# Sheet0.net
KiCad netlist of a schematic drawn in Altium Designer
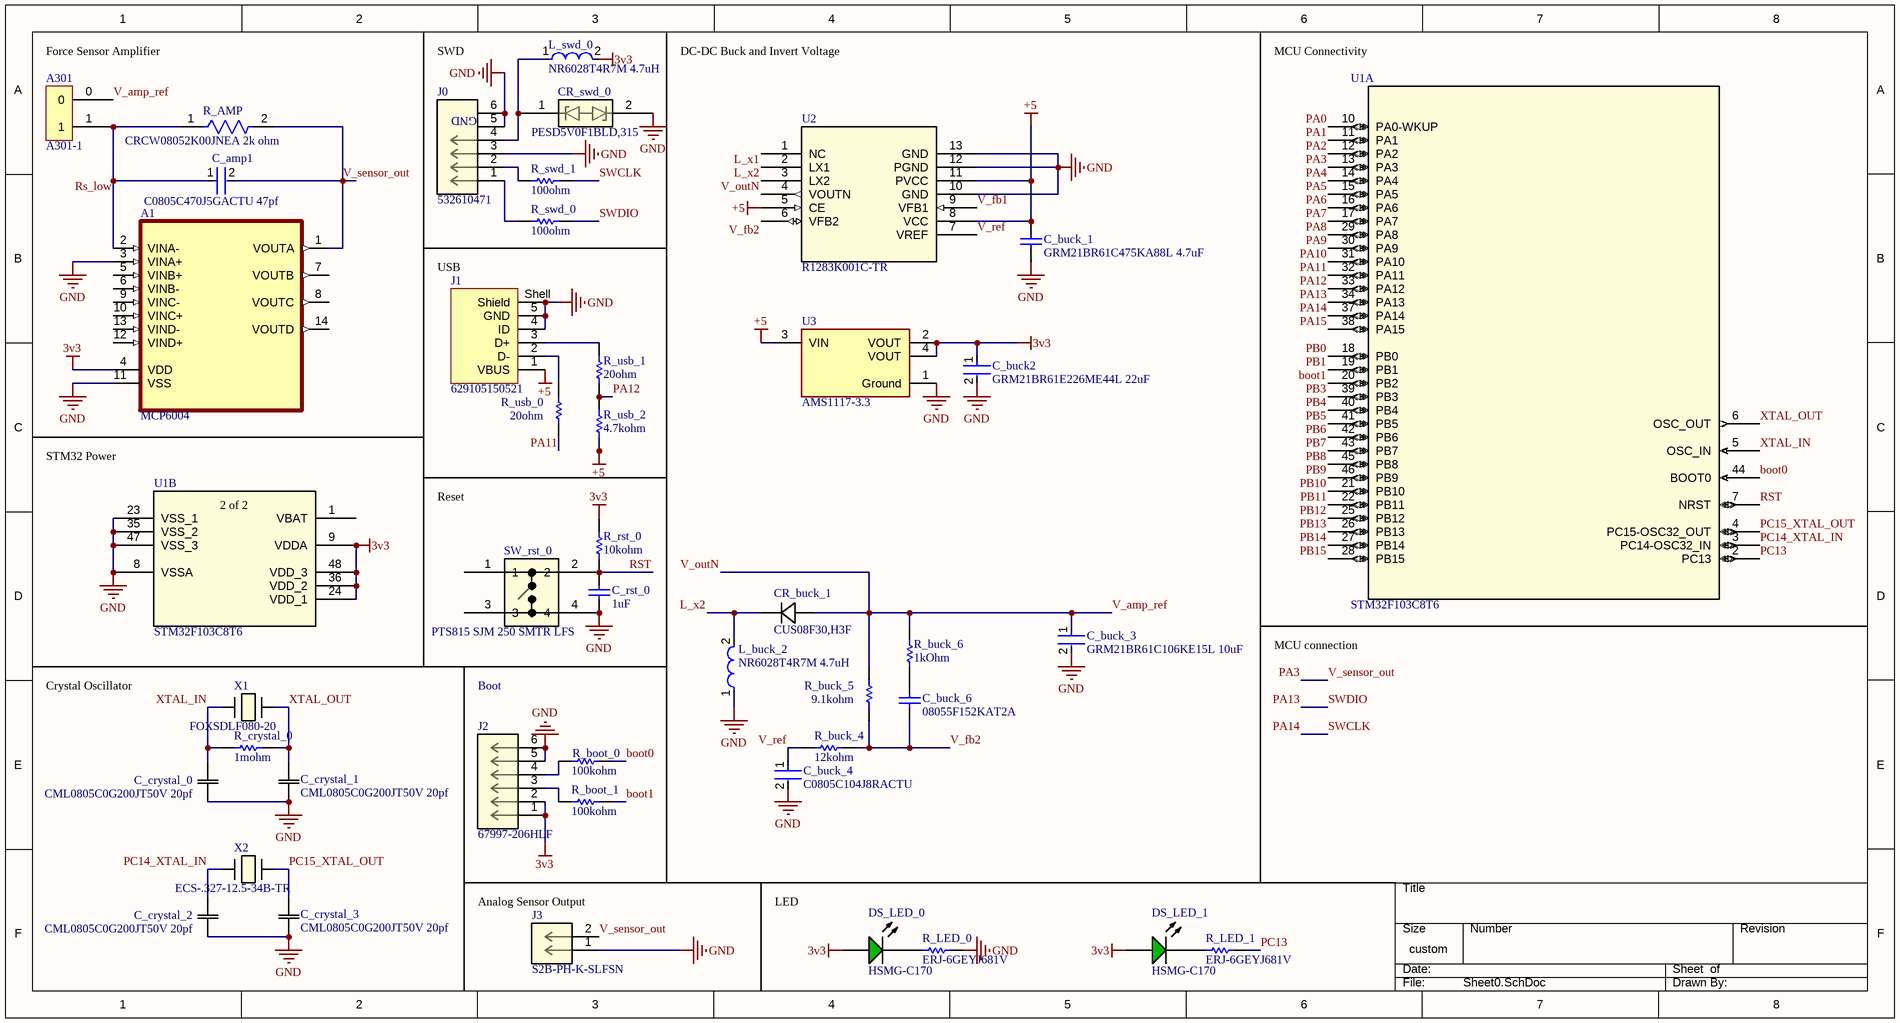
[diagram p0: Sheet0.SchDoc]

(export (version "E")
  (design (tool "Eeschema 10.0.6"))
  (components
    (comp (ref "A1")
      (value "MCP6004")
      (footprint "SOP65P640X120-14N")
      (libsource (lib "Schlib") (part "MCP6004"))
    )
    (comp (ref "A301") (value "A301-1") (footprint "A301-1") (libsource (lib "Schlib") (part "A301-1")))
    (comp (ref "CR_buck_1")
      (value "CUS08F30,H3F")
      (footprint "USC_TOS")
      (description "No Description Available")
      (libsource (lib "Schlib") (part "CUS08F30,H3F"))
    )
    (comp (ref "CR_swd_0")
      (value "PESD5V0F1BLD,315")
      (footprint "DFN1006D-2_SOD882D_NEX")
      (description "No Description Available")
      (libsource (lib "Schlib") (part "PESD5V0F1BLD,315"))
    )
    (comp (ref "C_amp1")
      (value "C0805C470J5GACTU 47pf")
      (footprint "FP-C0805C-DN-MFG")
      (description "CAP CER 47PF 50V C0G/NP0 0805")
      (fields
        (field (name "MANUFACTURER") "KEMET")
        (field (name "MANUFACTURER PART NUMBER") "C0805C470J5GACTU")
      )
      (libsource (lib "Altium Content Vault") (part "b4654b650e69147ec39a6b967a45e02"))
    )
    (comp (ref "C_buck2")
      (value "GRM21BR61E226ME44L 22uF")
      (footprint "FP-GRM21B-0_2-e0_2_0_7-IPC_B")
      (description "Chip Multilayer Ceramic Capacitors for General Purpose, 0805, 22uF, X5R, 15%, 20%, 25V")
      (fields (field (name "TOLERANCE") "20%") (field (name "VOLTAGE") "25V"))
      (libsource (lib "Altium Content Vault") (part "b4654b650e69147ec39a6b967a45e02"))
    )
    (comp (ref "C_buck_1")
      (value "GRM21BR61C475KA88L 4.7uF")
      (footprint "CAPC2013X135X45LL10T25")
      (description "Chip Capacitor, 4.7 uF, +/- 10%, 16 V, -55 to 85 degC, 0805 (2012 Metric), RoHS, Tape and Reel")
      (fields (field (name "TOLERANCE") "10%") (field (name "PARTNUMBER") "GRM21BR61C475KA88L"))
      (libsource (lib "Altium Content Vault") (part "CAP-NP-2"))
    )
    (comp (ref "C_buck_3")
      (value "GRM21BR61C106KE15L 10uF")
      (footprint "FP-GRM21B-0_1-IPC_C")
      (description "Chip Multilayer Ceramic Capacitors for General Purpose, 0805, 10uF, X5R, 15%, 10%, 16V")
      (fields (field (name "TOLERANCE") "10%") (field (name "VOLTAGE") "16V"))
      (libsource (lib "Altium Content Vault") (part "b4654b650e69147ec39a6b967a45e02"))
    )
    (comp (ref "C_buck_4")
      (value "C0805C104J8RACTU")
      (footprint "FP-C0805C-DN-MFG")
      (description "CAP CER 0.1UF 10V 5% X7R 0805")
      (fields (field (name "MANUFACTURER") "KEMET") (field (name "TOLERANCE") "0.05"))
      (libsource (lib "Altium Content Vault") (part "b4654b650e69147ec39a6b967a45e02"))
    )
    (comp (ref "C_buck_6")
      (value "08055F152KAT2A")
      (footprint "CAPC2013X140X50ML20T25")
      (fields (field (name "MANUFACTURER") "AVX Interconnect / Elco"))
      (libsource (lib "Altium Content Vault") (part "CAP"))
    )
    (comp (ref "C_crystal_0")
      (value "CML0805C0G200JT50V 20pf")
      (footprint "CAP_CML_0805_.3pF-1500pF,4700pF_STP")
      (description "No Description Available")
      (libsource (lib "Schlib") (part "CML0805C0G200JT50V"))
    )
    (comp (ref "C_crystal_1")
      (value "CML0805C0G200JT50V 20pf")
      (footprint "CAP_CML_0805_.3pF-1500pF,4700pF_STP")
      (description "No Description Available")
      (libsource (lib "Schlib") (part "CML0805C0G200JT50V"))
    )
    (comp (ref "C_crystal_2")
      (value "CML0805C0G200JT50V 20pf")
      (footprint "CAP_CML_0805_.3pF-1500pF,4700pF_STP")
      (description "No Description Available")
      (libsource (lib "Schlib") (part "CML0805C0G200JT50V"))
    )
    (comp (ref "C_crystal_3")
      (value "CML0805C0G200JT50V 20pf")
      (footprint "CAP_CML_0805_.3pF-1500pF,4700pF_STP")
      (description "No Description Available")
      (libsource (lib "Schlib") (part "CML0805C0G200JT50V"))
    )
    (comp (ref "C_rst_0")
      (value "1uF")
      (footprint "CAPC2013X140X50ML20T25")
      (fields (field (name "MANUFACTURER") "Kemet") (field (name "PART NUMBER") "C0805C105K5RACTU"))
      (libsource (lib "Altium Content Vault") (part "CAP"))
    )
    (comp (ref "DS_LED_0")
      (value "HSMG-C170")
      (footprint "AVAG-HSMX-C170_V")
      (description "Chip LED, Green, 2.2 V, -40 to 85 degC, 2-Pin SMD, Pb-Free, Tape and Reel")
      (fields (field (name "MANUFACTURER") "Avago"))
      (libsource (lib "Altium Content Vault") (part "LED_GREEN_A1K2-2"))
    )
    (comp (ref "DS_LED_1")
      (value "HSMG-C170")
      (footprint "AVAG-HSMX-C170_V")
      (description "Chip LED, Green, 2.2 V, -40 to 85 degC, 2-Pin SMD, Pb-Free, Tape and Reel")
      (fields (field (name "MANUFACTURER") "Avago"))
      (libsource (lib "Altium Content Vault") (part "LED_GREEN_A1K2-2"))
    )
    (comp (ref "J0")
      (value "532610471")
      (footprint "CONN_532610001-SD_04_MOL")
      (description "No Description Available")
      (libsource (lib "Schlib") (part "532610471"))
    )
    (comp (ref "J1")
      (value "629105150521")
      (footprint "629105150521")
      (libsource (lib "Altium Content Vault") (part "Micro USB 2.0_Type B_Receptacle_1 Port"))
    )
    (comp (ref "J2")
      (value "67997-206HLF")
      (footprint "6Pins_AMP")
      (description "No Description Available")
      (libsource (lib "Schlib") (part "67997-206HLF"))
    )
    (comp (ref "J3")
      (value "S2B-PH-K-SLFSN")
      (footprint "CONN_S2B-PH-K-S_JST")
      (description "No Description Available")
      (libsource (lib "Schlib") (part "S2B-PH-K-SLFSN"))
    )
    (comp (ref "L_buck_2")
      (value "NR6028T4R7M 4.7uH")
      (footprint "FP-NR6028-MFG")
      (description "SMD Power Inductors 4.7uH ±20% 2.7A 40.3mΩ")
      (fields (field (name "TOLERANCE") "20%"))
      (libsource (lib "Altium Content Vault") (part "725321dda6339637d4d059423bc1c3c"))
    )
    (comp (ref "L_swd_0")
      (value "NR6028T4R7M 4.7uH")
      (footprint "FP-NR6028-MFG")
      (description "SMD Power Inductors 4.7uH ±20% 2.7A 40.3mΩ")
      (fields (field (name "TOLERANCE") "20%"))
      (libsource (lib "Altium Content Vault") (part "725321dda6339637d4d059423bc1c3c"))
    )
    (comp (ref "R_AMP")
      (value "CRCW08052K00JNEA 2k ohm")
      (footprint "FP-CRCW0805-e3-MFG")
      (description "RES Thick Film, 2kΩ, 5%, 0.125W, 200ppm/°C, 0805")
      (fields (field (name "TOLERANCE") "5%"))
      (libsource (lib "Altium Content Vault") (part "1029c3af85768c4190bb7ad29bc67b5"))
    )
    (comp (ref "R_boot_0")
      (value "100kohm")
      (footprint "RESC2013X70X40ML20T20")
      (fields (field (name "PART NUMBER") "ERJ-6ENF1003V") (field (name "MANUFACTURER") "Panasonic"))
      (libsource (lib "Altium Content Vault") (part "RES"))
    )
    (comp (ref "R_boot_1")
      (value "100kohm")
      (footprint "RESC2013X70X40ML20T20")
      (fields (field (name "PART NUMBER") "ERJ-6ENF1003V") (field (name "MANUFACTURER") "Panasonic"))
      (libsource (lib "Altium Content Vault") (part "RES"))
    )
    (comp (ref "R_buck_4")
      (value "12kohm")
      (footprint "RESC2013X60X40ML20T25")
      (fields (field (name "PART NUMBER") "ERA6AEB123V") (field (name "MANUFACTURER") "Panasonic"))
      (libsource (lib "Altium Content Vault") (part "RES"))
    )
    (comp (ref "R_buck_5")
      (value "9.1kohm")
      (footprint "RESC2013X70X40NL20T20")
      (fields (field (name "PART NUMBER") "ERJ6ENF9101V") (field (name "MANUFACTURER") "Panasonic"))
      (libsource (lib "Altium Content Vault") (part "RES"))
    )
    (comp (ref "R_buck_6")
      (value "1kOhm")
      (footprint "RESC2013X60X35ML10T20")
      (description "Chip Resistor, 1 KOhm, +/- 1%, 125 mW, -55 to 155 degC, 0805 (2012 Metric), RoHS, Tape and Reel")
      (fields (field (name "TOLERANCE") "1%") (field (name "MANUFACTURER") "Yageo"))
      (libsource (lib "Altium Content Vault") (part "RES-2"))
    )
    (comp (ref "R_crystal_0")
      (value "1mohm")
      (footprint "RESC2013X50X30LL20T20")
      (fields (field (name "MANUFACTURER") "Vishay Dale") (field (name "PART NUMBER") "CRCW08051M00JNEA"))
      (libsource (lib "Altium Content Vault") (part "RES"))
    )
    (comp (ref "R_LED_0")
      (value "ERJ-6GEYJ681V")
      (footprint "RESC2013X70X40LL20T20")
      (fields (field (name "MANUFACTURER") "Panasonic"))
      (libsource (lib "Altium Content Vault") (part "RES"))
    )
    (comp (ref "R_LED_1")
      (value "ERJ-6GEYJ681V")
      (footprint "RESC2013X70X40LL20T20")
      (fields (field (name "MANUFACTURER") "Panasonic"))
      (libsource (lib "Altium Content Vault") (part "RES"))
    )
    (comp (ref "R_rst_0")
      (value "10kohm")
      (footprint "RESC2013X60X40LL20T25_A")
      (fields (field (name "TOLERANCE") "0.1%") (field (name "MANUFACTURER") "Panasonic"))
      (libsource (lib "Altium Content Vault") (part "RES-2"))
    )
    (comp (ref "R_swd_0")
      (value "100ohm")
      (footprint "RESC2013X60X40ML20T25")
      (fields (field (name "MANUFACTURER") "Panasonic") (field (name "PART NUMBER") "ERA6AEB101V"))
      (libsource (lib "Altium Content Vault") (part "RES"))
    )
    (comp (ref "R_swd_1")
      (value "100ohm")
      (footprint "RESC2013X60X40ML20T25")
      (fields (field (name "MANUFACTURER") "Panasonic") (field (name "PART NUMBER") "ERA6AEB101V"))
      (libsource (lib "Altium Content Vault") (part "RES"))
    )
    (comp (ref "R_usb_0")
      (value "20ohm")
      (footprint "RESC2013X70X40ML20T20")
      (fields (field (name "MANUFACTURER") "Panasonic") (field (name "PART NUMBER") "ERJ-6ENF20R0V"))
      (libsource (lib "Altium Content Vault") (part "RES"))
    )
    (comp (ref "R_usb_1")
      (value "20ohm")
      (footprint "RESC2013X70X40ML20T20")
      (fields (field (name "MANUFACTURER") "Panasonic") (field (name "PART NUMBER") "ERJ-6ENF20R0V"))
      (libsource (lib "Altium Content Vault") (part "RES"))
    )
    (comp (ref "R_usb_2")
      (value "4.7kohm")
      (footprint "RESC2013X60X40ML20T25")
      (fields (field (name "PART NUMBER") "ERA6AEB472V") (field (name "MANUFACTURER") "Panasonic"))
      (libsource (lib "Altium Content Vault") (part "RES"))
    )
    (comp (ref "SW_rst_0")
      (value "PTS815 SJM 250 SMTR LFS")
      (footprint "SW4_PTS815 SJM 250 SMTR LFS_CNK")
      (description "No Description Available")
      (libsource (lib "Schlib") (part "PTS815 SJM 250 SMTR LFS"))
    )
    (comp (ref "U1")
      (value "STM32F103C8T6")
      (footprint "LQFP48_STM")
      (description "No Description Available")
      (libsource (lib "Schlib") (part "STM32F103C8T6"))
    )
    (comp (ref "U2")
      (value "R1283K001C-TR")
      (footprint "PE-DFNPL2730-12-180404_NMD")
      (description "No Description Available")
      (libsource (lib "Schlib") (part "R1283K001C-TR"))
    )
    (comp (ref "U3")
      (value "AMS1117-3.3")
      (footprint "FP-AMS1117-IPC_C")
      (description "LDO Voltage Regulators 1A, 3.3V")
      (fields
        (field (name "OCTOPART") "https://octopart.com/ams1117-3.3-advanced+monolithic+systems-25899300")
        (field (name "MANUFACTURER") "Advanced Monolithic Systems")
      )
      (libsource (lib "Altium Content Vault") (part "8bdbb5f8e77002000e30dd2845d0354"))
    )
    (comp (ref "X1")
      (value "FOXSDLF080-20")
      (footprint "CRYSTAL_HC49SDLF_FXT")
      (description "No Description Available")
      (libsource (lib "Schlib") (part "FOXSDLF080-20"))
    )
    (comp (ref "X2")
      (value "ECS-.327-12.5-34B-TR")
      (footprint "XTAL_ECS-31B_ECS")
      (description "No Description Available")
      (libsource (lib "Schlib") (part "ECS-.327-12.5-34B-TR"))
    )
  )
  (nets
    (net (code "1") (name "+5") (class "Default")
      (node (ref "C_buck_1") (pin "2") (pinfunction "2_2") (pintype "passive"))
      (node (ref "J1") (pin "1") (pinfunction "VBUS_1") (pintype "passive"))
      (node (ref "R_usb_2") (pin "1") (pinfunction "1_1") (pintype "passive"))
      (node (ref "U2") (pin "11") (pinfunction "PVCC_11") (pintype "power_in"))
      (node (ref "U2") (pin "5") (pinfunction "CE_5") (pintype "input"))
      (node (ref "U2") (pin "8") (pinfunction "VCC_8") (pintype "power_in"))
      (node (ref "U3") (pin "3") (pinfunction "VIN_3") (pintype "power_in"))
    )
    (net (code "2") (name "/L_x1") (class "Default")
      (node (ref "U2") (pin "2") (pinfunction "LX1_2") (pintype "power_in"))
    )
    (net (code "3") (name "/L_x2") (class "Default")
      (node (ref "CR_buck_1") (pin "1") (pinfunction "cathode_1") (pintype "passive"))
      (node (ref "L_buck_2") (pin "2") (pinfunction "2_2") (pintype "passive"))
      (node (ref "U2") (pin "3") (pinfunction "LX2_3") (pintype "power_in"))
    )
    (net (code "4") (name "/PA0") (class "Default")
      (node (ref "U1") (pin "10") (pinfunction "PA0-WKUP_10") (pintype "bidirectional"))
    )
    (net (code "5") (name "/PA1") (class "Default")
      (node (ref "U1") (pin "11") (pinfunction "PA1_11") (pintype "bidirectional"))
    )
    (net (code "6") (name "/PA2") (class "Default")
      (node (ref "U1") (pin "12") (pinfunction "PA2_12") (pintype "bidirectional"))
    )
    (net (code "7") (name "/PA3") (class "Default")
      (node (ref "A1") (pin "1") (pinfunction "VOUTA_1") (pintype "output"))
      (node (ref "C_amp1") (pin "2") (pinfunction "2_2") (pintype "passive"))
      (node (ref "J3") (pin "2") (pinfunction "2_2") (pintype "passive"))
      (node (ref "R_AMP") (pin "2") (pinfunction "2_2") (pintype "passive"))
      (node (ref "U1") (pin "13") (pinfunction "PA3_13") (pintype "bidirectional"))
    )
    (net (code "8") (name "/PA4") (class "Default")
      (node (ref "U1") (pin "14") (pinfunction "PA4_14") (pintype "bidirectional"))
    )
    (net (code "9") (name "/PA5") (class "Default")
      (node (ref "U1") (pin "15") (pinfunction "PA5_15") (pintype "bidirectional"))
    )
    (net (code "10") (name "/PA6") (class "Default")
      (node (ref "U1") (pin "16") (pinfunction "PA6_16") (pintype "bidirectional"))
    )
    (net (code "11") (name "/PA7") (class "Default")
      (node (ref "U1") (pin "17") (pinfunction "PA7_17") (pintype "bidirectional"))
    )
    (net (code "12") (name "/PA8") (class "Default")
      (node (ref "U1") (pin "29") (pinfunction "PA8_29") (pintype "bidirectional"))
    )
    (net (code "13") (name "/PA9") (class "Default")
      (node (ref "U1") (pin "30") (pinfunction "PA9_30") (pintype "bidirectional"))
    )
    (net (code "14") (name "/PA10") (class "Default")
      (node (ref "U1") (pin "31") (pinfunction "PA10_31") (pintype "bidirectional"))
    )
    (net (code "15") (name "/PA11") (class "Default")
      (node (ref "R_usb_0") (pin "1") (pinfunction "1_1") (pintype "passive"))
      (node (ref "U1") (pin "32") (pinfunction "PA11_32") (pintype "bidirectional"))
    )
    (net (code "16") (name "/PA12") (class "Default")
      (node (ref "R_usb_1") (pin "1") (pinfunction "1_1") (pintype "passive"))
      (node (ref "R_usb_2") (pin "2") (pinfunction "2_2") (pintype "passive"))
      (node (ref "U1") (pin "33") (pinfunction "PA12_33") (pintype "bidirectional"))
    )
    (net (code "17") (name "/PA13") (class "Default")
      (node (ref "R_swd_0") (pin "2") (pinfunction "2_2") (pintype "passive"))
      (node (ref "U1") (pin "34") (pinfunction "PA13_34") (pintype "bidirectional"))
    )
    (net (code "18") (name "/PA14") (class "Default")
      (node (ref "R_swd_1") (pin "2") (pinfunction "2_2") (pintype "passive"))
      (node (ref "U1") (pin "37") (pinfunction "PA14_37") (pintype "bidirectional"))
    )
    (net (code "19") (name "/PA15") (class "Default")
      (node (ref "U1") (pin "38") (pinfunction "PA15_38") (pintype "bidirectional"))
    )
    (net (code "20") (name "/PB0") (class "Default")
      (node (ref "U1") (pin "18") (pinfunction "PB0_18") (pintype "bidirectional"))
    )
    (net (code "21") (name "/PB1") (class "Default")
      (node (ref "U1") (pin "19") (pinfunction "PB1_19") (pintype "bidirectional"))
    )
    (net (code "22") (name "/PB3") (class "Default")
      (node (ref "U1") (pin "39") (pinfunction "PB3_39") (pintype "bidirectional"))
    )
    (net (code "23") (name "/PB4") (class "Default")
      (node (ref "U1") (pin "40") (pinfunction "PB4_40") (pintype "bidirectional"))
    )
    (net (code "24") (name "/PB5") (class "Default")
      (node (ref "U1") (pin "41") (pinfunction "PB5_41") (pintype "bidirectional"))
    )
    (net (code "25") (name "/PB6") (class "Default")
      (node (ref "U1") (pin "42") (pinfunction "PB6_42") (pintype "bidirectional"))
    )
    (net (code "26") (name "/PB7") (class "Default")
      (node (ref "U1") (pin "43") (pinfunction "PB7_43") (pintype "bidirectional"))
    )
    (net (code "27") (name "/PB8") (class "Default")
      (node (ref "U1") (pin "45") (pinfunction "PB8_45") (pintype "bidirectional"))
    )
    (net (code "28") (name "/PB9") (class "Default")
      (node (ref "U1") (pin "46") (pinfunction "PB9_46") (pintype "bidirectional"))
    )
    (net (code "29") (name "/PB10") (class "Default")
      (node (ref "U1") (pin "21") (pinfunction "PB10_21") (pintype "bidirectional"))
    )
    (net (code "30") (name "/PB11") (class "Default")
      (node (ref "U1") (pin "22") (pinfunction "PB11_22") (pintype "bidirectional"))
    )
    (net (code "31") (name "/PB12") (class "Default")
      (node (ref "U1") (pin "25") (pinfunction "PB12_25") (pintype "bidirectional"))
    )
    (net (code "32") (name "/PB13") (class "Default")
      (node (ref "U1") (pin "26") (pinfunction "PB13_26") (pintype "bidirectional"))
    )
    (net (code "33") (name "/PB14") (class "Default")
      (node (ref "U1") (pin "27") (pinfunction "PB14_27") (pintype "bidirectional"))
    )
    (net (code "34") (name "/PB15") (class "Default")
      (node (ref "U1") (pin "28") (pinfunction "PB15_28") (pintype "bidirectional"))
    )
    (net (code "35") (name "/PC13") (class "Default")
      (node (ref "R_LED_1") (pin "2") (pinfunction "2_2") (pintype "passive"))
      (node (ref "U1") (pin "2") (pinfunction "PC13_2") (pintype "bidirectional"))
    )
    (net (code "36") (name "/PC14_XTAL_IN") (class "Default")
      (node (ref "C_crystal_2") (pin "2") (pinfunction "2_2") (pintype "passive"))
      (node (ref "U1") (pin "3") (pinfunction "PC14-OSC32_IN_3") (pintype "bidirectional"))
      (node (ref "X2") (pin "1") (pinfunction "1_1") (pintype "passive"))
    )
    (net (code "37") (name "/PC15_XTAL_OUT") (class "Default")
      (node (ref "C_crystal_3") (pin "2") (pinfunction "2_2") (pintype "passive"))
      (node (ref "U1") (pin "4") (pinfunction "PC15-OSC32_OUT_4") (pintype "bidirectional"))
      (node (ref "X2") (pin "2") (pinfunction "2_2") (pintype "passive"))
    )
    (net (code "38") (name "/RST") (class "Default")
      (node (ref "C_rst_0") (pin "2") (pinfunction "2_2") (pintype "passive"))
      (node (ref "R_rst_0") (pin "1") (pinfunction "1_1") (pintype "passive"))
      (node (ref "SW_rst_0") (pin "2") (pinfunction "2_2") (pintype "passive"))
      (node (ref "U1") (pin "7") (pinfunction "NRST_7") (pintype "bidirectional"))
    )
    (net (code "39") (name "/Rs_low") (class "Default")
      (node (ref "A1") (pin "2") (pinfunction "VINA-_2") (pintype "input"))
      (node (ref "A301") (pin "1") (pinfunction "1_1") (pintype "passive"))
      (node (ref "C_amp1") (pin "1") (pinfunction "1_1") (pintype "passive"))
      (node (ref "R_AMP") (pin "1") (pinfunction "1_1") (pintype "passive"))
    )
    (net (code "40") (name "/V_amp_ref") (class "Default")
      (node (ref "A301") (pin "0") (pinfunction "0_0") (pintype "passive"))
      (node (ref "CR_buck_1") (pin "2") (pinfunction "anode_2") (pintype "passive"))
      (node (ref "C_buck_3") (pin "1") (pinfunction "1_1") (pintype "passive"))
      (node (ref "R_buck_5") (pin "2") (pinfunction "2_2") (pintype "passive"))
      (node (ref "R_buck_6") (pin "2") (pinfunction "2_2") (pintype "passive"))
      (node (ref "U2") (pin "4") (pinfunction "VOUTN_4") (pintype "output"))
    )
    (net (code "41") (name "/V_fb1") (class "Default")
      (node (ref "U2") (pin "9") (pinfunction "VFB1_9") (pintype "input"))
    )
    (net (code "42") (name "/V_fb2") (class "Default")
      (node (ref "C_buck_6") (pin "1") (pinfunction "1_1") (pintype "passive"))
      (node (ref "R_buck_4") (pin "2") (pinfunction "2_2") (pintype "passive"))
      (node (ref "R_buck_5") (pin "1") (pinfunction "1_1") (pintype "passive"))
      (node (ref "U2") (pin "6") (pinfunction "VFB2_6") (pintype "bidirectional"))
    )
    (net (code "43") (name "/V_ref") (class "Default")
      (node (ref "C_buck_4") (pin "1") (pinfunction "1_1") (pintype "passive"))
      (node (ref "R_buck_4") (pin "1") (pinfunction "1_1") (pintype "passive"))
      (node (ref "U2") (pin "7") (pinfunction "VREF_7") (pintype "power_in"))
    )
    (net (code "44") (name "/XTAL_IN") (class "Default")
      (node (ref "C_crystal_0") (pin "2") (pinfunction "2_2") (pintype "passive"))
      (node (ref "R_crystal_0") (pin "1") (pinfunction "1_1") (pintype "passive"))
      (node (ref "U1") (pin "5") (pinfunction "OSC_IN_5") (pintype "input"))
      (node (ref "X1") (pin "1") (pinfunction "1_1") (pintype "passive"))
    )
    (net (code "45") (name "/XTAL_OUT") (class "Default")
      (node (ref "C_crystal_1") (pin "2") (pinfunction "2_2") (pintype "passive"))
      (node (ref "R_crystal_0") (pin "2") (pinfunction "2_2") (pintype "passive"))
      (node (ref "U1") (pin "6") (pinfunction "OSC_OUT_6") (pintype "output"))
      (node (ref "X1") (pin "2") (pinfunction "2_2") (pintype "passive"))
    )
    (net (code "46") (name "/boot0") (class "Default")
      (node (ref "R_boot_0") (pin "2") (pinfunction "2_2") (pintype "passive"))
      (node (ref "U1") (pin "44") (pinfunction "BOOT0_44") (pintype "input"))
    )
    (net (code "47") (name "/boot1") (class "Default")
      (node (ref "R_boot_1") (pin "2") (pinfunction "2_2") (pintype "passive"))
      (node (ref "U1") (pin "20") (pinfunction "PB2_20") (pintype "bidirectional"))
    )
    (net (code "48") (name "3v3") (class "Default")
      (node (ref "A1") (pin "4") (pinfunction "VDD_4") (pintype "power_in"))
      (node (ref "C_buck2") (pin "1") (pinfunction "1_1") (pintype "passive"))
      (node (ref "DS_LED_0") (pin "1") (pinfunction "A_1") (pintype "passive"))
      (node (ref "DS_LED_1") (pin "1") (pinfunction "A_1") (pintype "passive"))
      (node (ref "J2") (pin "1") (pinfunction "1_1") (pintype "passive"))
      (node (ref "J2") (pin "2") (pinfunction "2_2") (pintype "passive"))
      (node (ref "L_swd_0") (pin "2") (pinfunction "2_2") (pintype "passive"))
      (node (ref "R_rst_0") (pin "2") (pinfunction "2_2") (pintype "passive"))
      (node (ref "U1") (pin "24") (pinfunction "VDD_1_24") (pintype "power_in"))
      (node (ref "U1") (pin "36") (pinfunction "VDD_2_36") (pintype "power_in"))
      (node (ref "U1") (pin "48") (pinfunction "VDD_3_48") (pintype "power_in"))
      (node (ref "U1") (pin "9") (pinfunction "VDDA_9") (pintype "power_in"))
      (node (ref "U3") (pin "2") (pinfunction "VOUT_2") (pintype "passive"))
      (node (ref "U3") (pin "4") (pinfunction "VOUT_4") (pintype "passive"))
    )
    (net (code "49") (name "GND") (class "Default")
      (node (ref "A1") (pin "11") (pinfunction "VSS_11") (pintype "passive"))
      (node (ref "A1") (pin "3") (pinfunction "VINA+_3") (pintype "input"))
      (node (ref "CR_swd_0") (pin "2") (pinfunction "2_2") (pintype "passive"))
      (node (ref "C_buck2") (pin "2") (pinfunction "2_2") (pintype "passive"))
      (node (ref "C_buck_1") (pin "1") (pinfunction "1_1") (pintype "passive"))
      (node (ref "C_buck_3") (pin "2") (pinfunction "2_2") (pintype "passive"))
      (node (ref "C_buck_4") (pin "2") (pinfunction "2_2") (pintype "passive"))
      (node (ref "C_crystal_0") (pin "1") (pinfunction "1_1") (pintype "passive"))
      (node (ref "C_crystal_1") (pin "1") (pinfunction "1_1") (pintype "passive"))
      (node (ref "C_crystal_2") (pin "1") (pinfunction "1_1") (pintype "passive"))
      (node (ref "C_crystal_3") (pin "1") (pinfunction "1_1") (pintype "passive"))
      (node (ref "C_rst_0") (pin "1") (pinfunction "1_1") (pintype "passive"))
      (node (ref "J0") (pin "3") (pinfunction "3_3") (pintype "passive"))
      (node (ref "J0") (pin "5") (pinfunction "5_5") (pintype "passive"))
      (node (ref "J0") (pin "6") (pinfunction "6_6") (pintype "passive"))
      (node (ref "J1") (pin "4") (pinfunction "ID_4") (pintype "passive"))
      (node (ref "J1") (pin "5") (pinfunction "GND_5") (pintype "passive"))
      (node (ref "J1") (pin "Shell") (pinfunction "Shield_Shell") (pintype "passive"))
      (node (ref "J2") (pin "5") (pinfunction "5_5") (pintype "passive"))
      (node (ref "J2") (pin "6") (pinfunction "6_6") (pintype "passive"))
      (node (ref "J3") (pin "1") (pinfunction "1_1") (pintype "passive"))
      (node (ref "L_buck_2") (pin "1") (pinfunction "1_1") (pintype "passive"))
      (node (ref "R_LED_0") (pin "2") (pinfunction "2_2") (pintype "passive"))
      (node (ref "SW_rst_0") (pin "4") (pinfunction "4_4") (pintype "passive"))
      (node (ref "U1") (pin "23") (pinfunction "VSS_1_23") (pintype "power_in"))
      (node (ref "U1") (pin "35") (pinfunction "VSS_2_35") (pintype "power_in"))
      (node (ref "U1") (pin "47") (pinfunction "VSS_3_47") (pintype "power_in"))
      (node (ref "U1") (pin "8") (pinfunction "VSSA_8") (pintype "power_in"))
      (node (ref "U2") (pin "10") (pinfunction "GND_10") (pintype "power_in"))
      (node (ref "U2") (pin "12") (pinfunction "PGND_12") (pintype "power_in"))
      (node (ref "U2") (pin "13") (pinfunction "GND_13") (pintype "power_in"))
      (node (ref "U3") (pin "1") (pinfunction "Ground_1") (pintype "power_in"))
    )
    (net (code "50") (name "Net-(CR_swd_0-Pad1)") (class "Default")
      (node (ref "CR_swd_0") (pin "1") (pinfunction "1_1") (pintype "passive"))
      (node (ref "J0") (pin "4") (pinfunction "4_4") (pintype "passive"))
      (node (ref "L_swd_0") (pin "1") (pinfunction "1_1") (pintype "passive"))
    )
    (net (code "51") (name "Net-(C_buck_6-Pad2)") (class "Default")
      (node (ref "C_buck_6") (pin "2") (pinfunction "2_2") (pintype "passive"))
      (node (ref "R_buck_6") (pin "1") (pinfunction "1_1") (pintype "passive"))
    )
    (net (code "52") (name "Net-(DS_LED_0-K)") (class "Default")
      (node (ref "DS_LED_0") (pin "2") (pinfunction "K_2") (pintype "passive"))
      (node (ref "R_LED_0") (pin "1") (pinfunction "1_1") (pintype "passive"))
    )
    (net (code "53") (name "Net-(DS_LED_1-K)") (class "Default")
      (node (ref "DS_LED_1") (pin "2") (pinfunction "K_2") (pintype "passive"))
      (node (ref "R_LED_1") (pin "1") (pinfunction "1_1") (pintype "passive"))
    )
    (net (code "54") (name "Net-(J0-Pad1)") (class "Default")
      (node (ref "J0") (pin "1") (pinfunction "1_1") (pintype "passive"))
      (node (ref "R_swd_0") (pin "1") (pinfunction "1_1") (pintype "passive"))
    )
    (net (code "55") (name "Net-(J0-Pad2)") (class "Default")
      (node (ref "J0") (pin "2") (pinfunction "2_2") (pintype "passive"))
      (node (ref "R_swd_1") (pin "1") (pinfunction "1_1") (pintype "passive"))
    )
    (net (code "56") (name "Net-(J1-D+)") (class "Default")
      (node (ref "J1") (pin "3") (pinfunction "D+_3") (pintype "passive"))
      (node (ref "R_usb_1") (pin "2") (pinfunction "2_2") (pintype "passive"))
    )
    (net (code "57") (name "Net-(J1-D-)") (class "Default")
      (node (ref "J1") (pin "2") (pinfunction "D-_2") (pintype "passive"))
      (node (ref "R_usb_0") (pin "2") (pinfunction "2_2") (pintype "passive"))
    )
    (net (code "58") (name "Net-(J2-Pad3)") (class "Default")
      (node (ref "J2") (pin "3") (pinfunction "3_3") (pintype "passive"))
      (node (ref "R_boot_1") (pin "1") (pinfunction "1_1") (pintype "passive"))
    )
    (net (code "59") (name "Net-(J2-Pad4)") (class "Default")
      (node (ref "J2") (pin "4") (pinfunction "4_4") (pintype "passive"))
      (node (ref "R_boot_0") (pin "1") (pinfunction "1_1") (pintype "passive"))
    )
    (net (code "60") (name "unconnected-(A1-VINB+-Pad5)") (class "Default")
      (node (ref "A1") (pin "5") (pinfunction "VINB+_5") (pintype "input"))
    )
    (net (code "61") (name "unconnected-(A1-VINB--Pad6)") (class "Default")
      (node (ref "A1") (pin "6") (pinfunction "VINB-_6") (pintype "input"))
    )
    (net (code "62") (name "unconnected-(A1-VINC+-Pad10)") (class "Default")
      (node (ref "A1") (pin "10") (pinfunction "VINC+_10") (pintype "input"))
    )
    (net (code "63") (name "unconnected-(A1-VINC--Pad9)") (class "Default")
      (node (ref "A1") (pin "9") (pinfunction "VINC-_9") (pintype "input"))
    )
    (net (code "64") (name "unconnected-(A1-VIND+-Pad12)") (class "Default")
      (node (ref "A1") (pin "12") (pinfunction "VIND+_12") (pintype "input"))
    )
    (net (code "65") (name "unconnected-(A1-VIND--Pad13)") (class "Default")
      (node (ref "A1") (pin "13") (pinfunction "VIND-_13") (pintype "input"))
    )
    (net (code "66") (name "unconnected-(A1-VOUTB-Pad7)") (class "Default")
      (node (ref "A1") (pin "7") (pinfunction "VOUTB_7") (pintype "output"))
    )
    (net (code "67") (name "unconnected-(A1-VOUTC-Pad8)") (class "Default")
      (node (ref "A1") (pin "8") (pinfunction "VOUTC_8") (pintype "output"))
    )
    (net (code "68") (name "unconnected-(A1-VOUTD-Pad14)") (class "Default")
      (node (ref "A1") (pin "14") (pinfunction "VOUTD_14") (pintype "output"))
    )
    (net (code "69") (name "unconnected-(SW_rst_0-Pad1)") (class "Default")
      (node (ref "SW_rst_0") (pin "1") (pinfunction "1_1") (pintype "passive"))
    )
    (net (code "70") (name "unconnected-(SW_rst_0-Pad3)") (class "Default")
      (node (ref "SW_rst_0") (pin "3") (pinfunction "3_3") (pintype "passive"))
    )
    (net (code "71") (name "unconnected-(U1B-VBAT-Pad1)") (class "Default")
      (node (ref "U1") (pin "1") (pinfunction "VBAT_1") (pintype "power_in"))
    )
    (net (code "72") (name "unconnected-(U2-NC-Pad1)") (class "Default")
      (node (ref "U2") (pin "1") (pinfunction "NC_1") (pintype "passive"))
    )
  )
)
